# dac-misc.net
KiCad netlist of a schematic drawn in Altium Designer
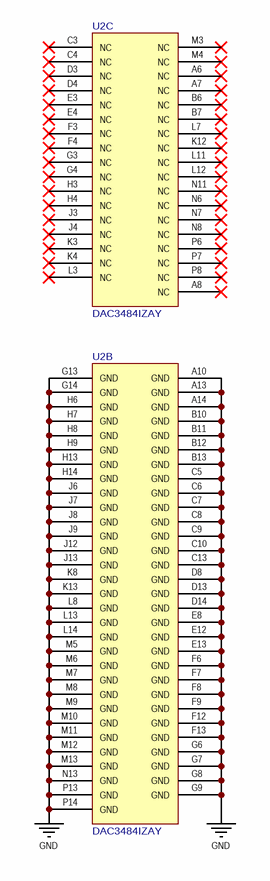
[diagram p0: dac-misc.SchDoc]

(export (version "E")
  (design (tool "Eeschema 10.0.6"))
  (components
    (comp (ref "U2")
      (value "DAC3484IZAY")
      (footprint "ZAY-BGA-196")
      (description "High Speed Quad DAC, 16-bit, 1.25GSPS")
      (fields (field (name "MANUFACTURER") "Texas Instruments"))
      (libsource (lib "ti") (part "DAC3484IZAY"))
    )
  )
  (nets
    (net (code "1") (name "GND") (class "Default")
      (node (ref "U2") (pin "A10") (pinfunction "GND_A10") (pintype "power_in"))
      (node (ref "U2") (pin "A13") (pinfunction "GND_A13") (pintype "power_in"))
      (node (ref "U2") (pin "A14") (pinfunction "GND_A14") (pintype "power_in"))
      (node (ref "U2") (pin "B10") (pinfunction "GND_B10") (pintype "power_in"))
      (node (ref "U2") (pin "B11") (pinfunction "GND_B11") (pintype "power_in"))
      (node (ref "U2") (pin "B12") (pinfunction "GND_B12") (pintype "power_in"))
      (node (ref "U2") (pin "B13") (pinfunction "GND_B13") (pintype "power_in"))
      (node (ref "U2") (pin "C10") (pinfunction "GND_C10") (pintype "power_in"))
      (node (ref "U2") (pin "C13") (pinfunction "GND_C13") (pintype "power_in"))
      (node (ref "U2") (pin "C5") (pinfunction "GND_C5") (pintype "power_in"))
      (node (ref "U2") (pin "C6") (pinfunction "GND_C6") (pintype "power_in"))
      (node (ref "U2") (pin "C7") (pinfunction "GND_C7") (pintype "power_in"))
      (node (ref "U2") (pin "C8") (pinfunction "GND_C8") (pintype "power_in"))
      (node (ref "U2") (pin "C9") (pinfunction "GND_C9") (pintype "power_in"))
      (node (ref "U2") (pin "D13") (pinfunction "GND_D13") (pintype "power_in"))
      (node (ref "U2") (pin "D14") (pinfunction "GND_D14") (pintype "power_in"))
      (node (ref "U2") (pin "D8") (pinfunction "GND_D8") (pintype "power_in"))
      (node (ref "U2") (pin "E12") (pinfunction "GND_E12") (pintype "power_in"))
      (node (ref "U2") (pin "E13") (pinfunction "GND_E13") (pintype "power_in"))
      (node (ref "U2") (pin "E8") (pinfunction "GND_E8") (pintype "power_in"))
      (node (ref "U2") (pin "F12") (pinfunction "GND_F12") (pintype "power_in"))
      (node (ref "U2") (pin "F13") (pinfunction "GND_F13") (pintype "power_in"))
      (node (ref "U2") (pin "F6") (pinfunction "GND_F6") (pintype "power_in"))
      (node (ref "U2") (pin "F7") (pinfunction "GND_F7") (pintype "power_in"))
      (node (ref "U2") (pin "F8") (pinfunction "GND_F8") (pintype "power_in"))
      (node (ref "U2") (pin "F9") (pinfunction "GND_F9") (pintype "power_in"))
      (node (ref "U2") (pin "G13") (pinfunction "GND_G13") (pintype "power_in"))
      (node (ref "U2") (pin "G14") (pinfunction "GND_G14") (pintype "power_in"))
      (node (ref "U2") (pin "G6") (pinfunction "GND_G6") (pintype "power_in"))
      (node (ref "U2") (pin "G7") (pinfunction "GND_G7") (pintype "power_in"))
      (node (ref "U2") (pin "G8") (pinfunction "GND_G8") (pintype "power_in"))
      (node (ref "U2") (pin "G9") (pinfunction "GND_G9") (pintype "power_in"))
      (node (ref "U2") (pin "H13") (pinfunction "GND_H13") (pintype "power_in"))
      (node (ref "U2") (pin "H14") (pinfunction "GND_H14") (pintype "power_in"))
      (node (ref "U2") (pin "H6") (pinfunction "GND_H6") (pintype "power_in"))
      (node (ref "U2") (pin "H7") (pinfunction "GND_H7") (pintype "power_in"))
      (node (ref "U2") (pin "H8") (pinfunction "GND_H8") (pintype "power_in"))
      (node (ref "U2") (pin "H9") (pinfunction "GND_H9") (pintype "power_in"))
      (node (ref "U2") (pin "J12") (pinfunction "GND_J12") (pintype "power_in"))
      (node (ref "U2") (pin "J13") (pinfunction "GND_J13") (pintype "power_in"))
      (node (ref "U2") (pin "J6") (pinfunction "GND_J6") (pintype "power_in"))
      (node (ref "U2") (pin "J7") (pinfunction "GND_J7") (pintype "power_in"))
      (node (ref "U2") (pin "J8") (pinfunction "GND_J8") (pintype "power_in"))
      (node (ref "U2") (pin "J9") (pinfunction "GND_J9") (pintype "power_in"))
      (node (ref "U2") (pin "K13") (pinfunction "GND_K13") (pintype "power_in"))
      (node (ref "U2") (pin "K8") (pinfunction "GND_K8") (pintype "power_in"))
      (node (ref "U2") (pin "L13") (pinfunction "GND_L13") (pintype "power_in"))
      (node (ref "U2") (pin "L14") (pinfunction "GND_L14") (pintype "power_in"))
      (node (ref "U2") (pin "L8") (pinfunction "GND_L8") (pintype "power_in"))
      (node (ref "U2") (pin "M10") (pinfunction "GND_M10") (pintype "power_in"))
      (node (ref "U2") (pin "M11") (pinfunction "GND_M11") (pintype "power_in"))
      (node (ref "U2") (pin "M12") (pinfunction "GND_M12") (pintype "power_in"))
      (node (ref "U2") (pin "M13") (pinfunction "GND_M13") (pintype "power_in"))
      (node (ref "U2") (pin "M5") (pinfunction "GND_M5") (pintype "power_in"))
      (node (ref "U2") (pin "M6") (pinfunction "GND_M6") (pintype "power_in"))
      (node (ref "U2") (pin "M7") (pinfunction "GND_M7") (pintype "power_in"))
      (node (ref "U2") (pin "M8") (pinfunction "GND_M8") (pintype "power_in"))
      (node (ref "U2") (pin "M9") (pinfunction "GND_M9") (pintype "power_in"))
      (node (ref "U2") (pin "N13") (pinfunction "GND_N13") (pintype "power_in"))
      (node (ref "U2") (pin "P13") (pinfunction "GND_P13") (pintype "power_in"))
      (node (ref "U2") (pin "P14") (pinfunction "GND_P14") (pintype "power_in"))
    )
    (net (code "2") (name "unconnected-(U2C-NC-PadA6)") (class "Default")
      (node (ref "U2") (pin "A6") (pinfunction "NC_A6") (pintype "power_in+no_connect"))
    )
    (net (code "3") (name "unconnected-(U2C-NC-PadA7)") (class "Default")
      (node (ref "U2") (pin "A7") (pinfunction "NC_A7") (pintype "power_in+no_connect"))
    )
    (net (code "4") (name "unconnected-(U2C-NC-PadA8)") (class "Default")
      (node (ref "U2") (pin "A8") (pinfunction "NC_A8") (pintype "passive+no_connect"))
    )
    (net (code "5") (name "unconnected-(U2C-NC-PadB6)") (class "Default")
      (node (ref "U2") (pin "B6") (pinfunction "NC_B6") (pintype "power_in+no_connect"))
    )
    (net (code "6") (name "unconnected-(U2C-NC-PadB7)") (class "Default")
      (node (ref "U2") (pin "B7") (pinfunction "NC_B7") (pintype "power_in+no_connect"))
    )
    (net (code "7") (name "unconnected-(U2C-NC-PadC3)") (class "Default")
      (node (ref "U2") (pin "C3") (pinfunction "NC_C3") (pintype "power_in+no_connect"))
    )
    (net (code "8") (name "unconnected-(U2C-NC-PadC4)") (class "Default")
      (node (ref "U2") (pin "C4") (pinfunction "NC_C4") (pintype "power_in+no_connect"))
    )
    (net (code "9") (name "unconnected-(U2C-NC-PadD3)") (class "Default")
      (node (ref "U2") (pin "D3") (pinfunction "NC_D3") (pintype "power_in+no_connect"))
    )
    (net (code "10") (name "unconnected-(U2C-NC-PadD4)") (class "Default")
      (node (ref "U2") (pin "D4") (pinfunction "NC_D4") (pintype "power_in+no_connect"))
    )
    (net (code "11") (name "unconnected-(U2C-NC-PadE3)") (class "Default")
      (node (ref "U2") (pin "E3") (pinfunction "NC_E3") (pintype "power_in+no_connect"))
    )
    (net (code "12") (name "unconnected-(U2C-NC-PadE4)") (class "Default")
      (node (ref "U2") (pin "E4") (pinfunction "NC_E4") (pintype "power_in+no_connect"))
    )
    (net (code "13") (name "unconnected-(U2C-NC-PadF3)") (class "Default")
      (node (ref "U2") (pin "F3") (pinfunction "NC_F3") (pintype "power_in+no_connect"))
    )
    (net (code "14") (name "unconnected-(U2C-NC-PadF4)") (class "Default")
      (node (ref "U2") (pin "F4") (pinfunction "NC_F4") (pintype "power_in+no_connect"))
    )
    (net (code "15") (name "unconnected-(U2C-NC-PadG3)") (class "Default")
      (node (ref "U2") (pin "G3") (pinfunction "NC_G3") (pintype "power_in+no_connect"))
    )
    (net (code "16") (name "unconnected-(U2C-NC-PadG4)") (class "Default")
      (node (ref "U2") (pin "G4") (pinfunction "NC_G4") (pintype "power_in+no_connect"))
    )
    (net (code "17") (name "unconnected-(U2C-NC-PadH3)") (class "Default")
      (node (ref "U2") (pin "H3") (pinfunction "NC_H3") (pintype "power_in+no_connect"))
    )
    (net (code "18") (name "unconnected-(U2C-NC-PadH4)") (class "Default")
      (node (ref "U2") (pin "H4") (pinfunction "NC_H4") (pintype "power_in+no_connect"))
    )
    (net (code "19") (name "unconnected-(U2C-NC-PadJ3)") (class "Default")
      (node (ref "U2") (pin "J3") (pinfunction "NC_J3") (pintype "power_in+no_connect"))
    )
    (net (code "20") (name "unconnected-(U2C-NC-PadJ4)") (class "Default")
      (node (ref "U2") (pin "J4") (pinfunction "NC_J4") (pintype "power_in+no_connect"))
    )
    (net (code "21") (name "unconnected-(U2C-NC-PadK3)") (class "Default")
      (node (ref "U2") (pin "K3") (pinfunction "NC_K3") (pintype "power_in+no_connect"))
    )
    (net (code "22") (name "unconnected-(U2C-NC-PadK4)") (class "Default")
      (node (ref "U2") (pin "K4") (pinfunction "NC_K4") (pintype "power_in+no_connect"))
    )
    (net (code "23") (name "unconnected-(U2C-NC-PadK12)") (class "Default")
      (node (ref "U2") (pin "K12") (pinfunction "NC_K12") (pintype "power_in+no_connect"))
    )
    (net (code "24") (name "unconnected-(U2C-NC-PadL3)") (class "Default")
      (node (ref "U2") (pin "L3") (pinfunction "NC_L3") (pintype "power_in+no_connect"))
    )
    (net (code "25") (name "unconnected-(U2C-NC-PadL7)") (class "Default")
      (node (ref "U2") (pin "L7") (pinfunction "NC_L7") (pintype "power_in+no_connect"))
    )
    (net (code "26") (name "unconnected-(U2C-NC-PadL11)") (class "Default")
      (node (ref "U2") (pin "L11") (pinfunction "NC_L11") (pintype "power_in+no_connect"))
    )
    (net (code "27") (name "unconnected-(U2C-NC-PadL12)") (class "Default")
      (node (ref "U2") (pin "L12") (pinfunction "NC_L12") (pintype "power_in+no_connect"))
    )
    (net (code "28") (name "unconnected-(U2C-NC-PadM3)") (class "Default")
      (node (ref "U2") (pin "M3") (pinfunction "NC_M3") (pintype "power_in+no_connect"))
    )
    (net (code "29") (name "unconnected-(U2C-NC-PadM4)") (class "Default")
      (node (ref "U2") (pin "M4") (pinfunction "NC_M4") (pintype "power_in+no_connect"))
    )
    (net (code "30") (name "unconnected-(U2C-NC-PadN6)") (class "Default")
      (node (ref "U2") (pin "N6") (pinfunction "NC_N6") (pintype "power_in+no_connect"))
    )
    (net (code "31") (name "unconnected-(U2C-NC-PadN7)") (class "Default")
      (node (ref "U2") (pin "N7") (pinfunction "NC_N7") (pintype "power_in+no_connect"))
    )
    (net (code "32") (name "unconnected-(U2C-NC-PadN8)") (class "Default")
      (node (ref "U2") (pin "N8") (pinfunction "NC_N8") (pintype "power_in+no_connect"))
    )
    (net (code "33") (name "unconnected-(U2C-NC-PadN11)") (class "Default")
      (node (ref "U2") (pin "N11") (pinfunction "NC_N11") (pintype "power_in+no_connect"))
    )
    (net (code "34") (name "unconnected-(U2C-NC-PadP6)") (class "Default")
      (node (ref "U2") (pin "P6") (pinfunction "NC_P6") (pintype "power_in+no_connect"))
    )
    (net (code "35") (name "unconnected-(U2C-NC-PadP7)") (class "Default")
      (node (ref "U2") (pin "P7") (pinfunction "NC_P7") (pintype "power_in+no_connect"))
    )
    (net (code "36") (name "unconnected-(U2C-NC-PadP8)") (class "Default")
      (node (ref "U2") (pin "P8") (pinfunction "NC_P8") (pintype "power_in+no_connect"))
    )
  )
)
